# BleHidKeyboard.net
KiCad netlist of a schematic drawn in EAGLE
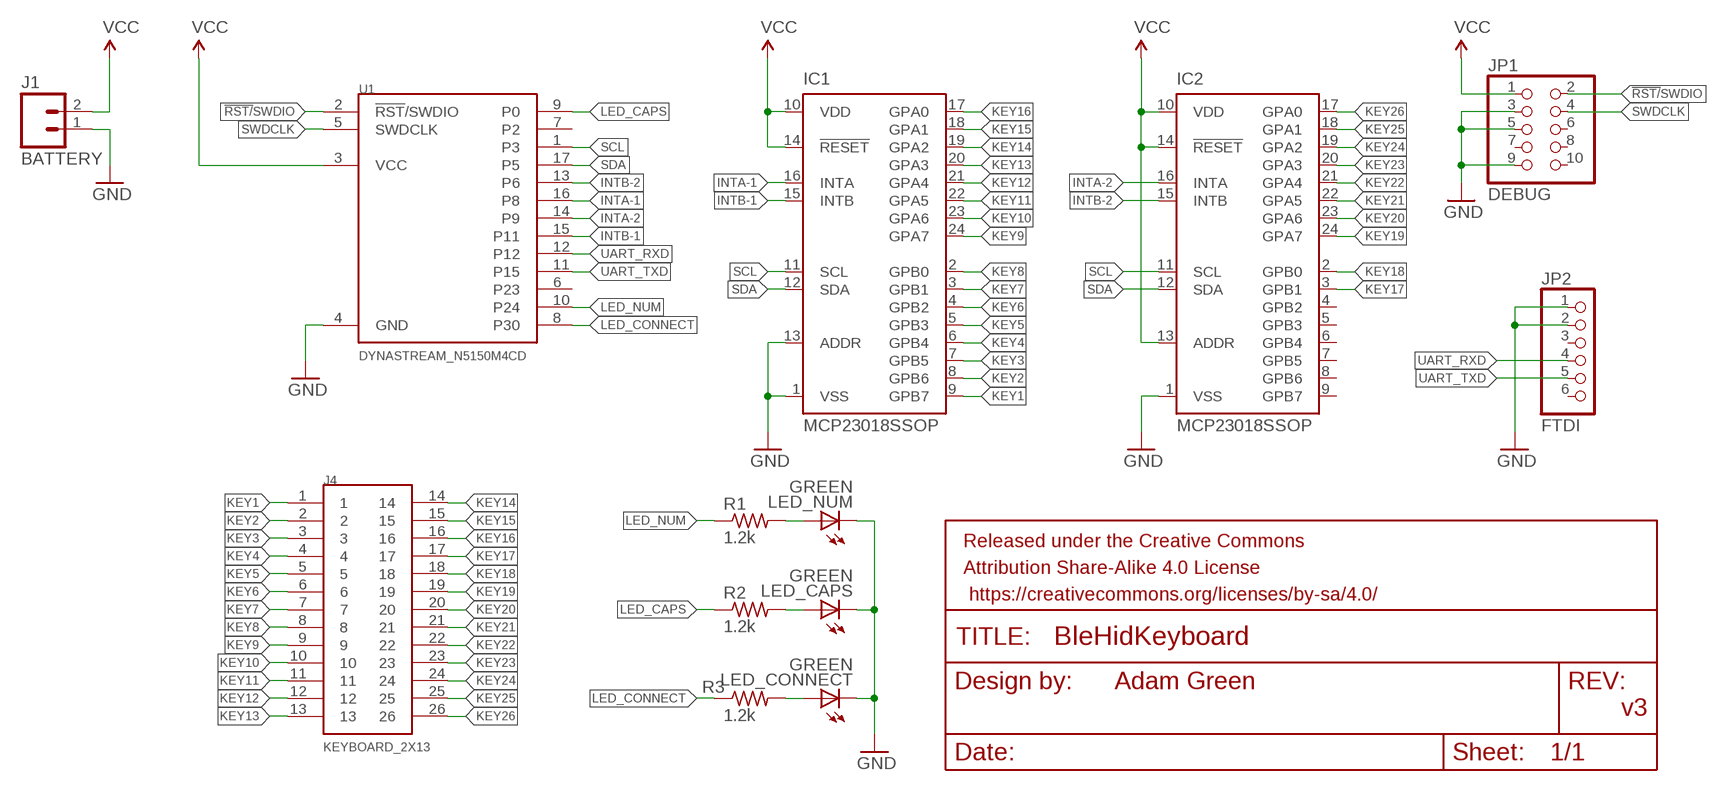
[diagram p0: schematic, sheet 1]

(export (version "E")
  (design (tool "Eeschema 10.0.6"))
  (components
    (comp (ref "IC1")
      (value "MCP23018SSOP")
      (footprint "eagle-import:SSOP24")
      (libsource (lib "eagle-import") (part "MCP23018SSOP"))
    )
    (comp (ref "IC2")
      (value "MCP23018SSOP")
      (footprint "eagle-import:SSOP24")
      (libsource (lib "eagle-import") (part "MCP23018SSOP"))
    )
    (comp (ref "J1")
      (value "BATTERY")
      (footprint "eagle-import:1X02_NO_SILK")
      (libsource (lib "eagle-import") (part "M021X02_NO_SILK"))
    )
    (comp (ref "J4")
      (value "KEYBOARD_2X13")
      (footprint "eagle-import:KEYBOARD_2X13")
      (libsource (lib "eagle-import") (part "KEYBOARD_2X13"))
    )
    (comp (ref "JP1")
      (value "DEBUG")
      (footprint "eagle-import:FTSH-105")
      (libsource (lib "eagle-import") (part "FTSH-105"))
    )
    (comp (ref "JP2")
      (value "FTDI")
      (footprint "eagle-import:1X06-CLEAN")
      (libsource (lib "eagle-import") (part "PINHD-1X6CLEAN"))
    )
    (comp (ref "LED_CAPS")
      (value "GREEN")
      (footprint "eagle-import:CHIPLED_1206")
      (libsource (lib "eagle-import") (part "LEDCHIPLED_1206"))
    )
    (comp (ref "LED_CONNECT")
      (value "GREEN")
      (footprint "eagle-import:CHIPLED_1206")
      (libsource (lib "eagle-import") (part "LEDCHIPLED_1206"))
    )
    (comp (ref "LED_NUM")
      (value "GREEN")
      (footprint "eagle-import:CHIPLED_1206")
      (libsource (lib "eagle-import") (part "LEDCHIPLED_1206"))
    )
    (comp (ref "R1")
      (value "1.2k")
      (footprint "eagle-import:R0805")
      (libsource (lib "eagle-import") (part "R-US_R0805"))
    )
    (comp (ref "R2")
      (value "1.2k")
      (footprint "eagle-import:R0805")
      (libsource (lib "eagle-import") (part "R-US_R0805"))
    )
    (comp (ref "R3")
      (value "1.2k")
      (footprint "eagle-import:R0805")
      (libsource (lib "eagle-import") (part "R-US_R0805"))
    )
    (comp (ref "U1")
      (value "DYNASTREAM_N5150M4CD")
      (footprint "eagle-import:N5150M4CD")
      (libsource (lib "eagle-import") (part "DYNASTREAM_N5150M4CD"))
    )
  )
  (nets
    (net (code "1") (name "/~{RST{slash}}SWDIO") (class "Default")
      (node (ref "JP1") (pin "2") (pinfunction "2_2") (pintype "passive"))
      (node (ref "U1") (pin "2") (pinfunction "~{RST}/SWDIO_2") (pintype "bidirectional"))
    )
    (net (code "2") (name "GND") (class "Default")
      (node (ref "IC1") (pin "1") (pinfunction "VSS_1") (pintype "input"))
      (node (ref "IC1") (pin "13") (pinfunction "ADDR_13") (pintype "input"))
      (node (ref "IC2") (pin "1") (pinfunction "VSS_1") (pintype "input"))
      (node (ref "J1") (pin "1") (pinfunction "1_1") (pintype "passive"))
      (node (ref "JP1") (pin "3") (pinfunction "3_3") (pintype "passive"))
      (node (ref "JP1") (pin "5") (pinfunction "5_5") (pintype "passive"))
      (node (ref "JP1") (pin "9") (pinfunction "9_9") (pintype "passive"))
      (node (ref "JP2") (pin "1") (pinfunction "1_1") (pintype "passive"))
      (node (ref "JP2") (pin "2") (pinfunction "2_2") (pintype "passive"))
      (node (ref "LED_CAPS") (pin "C") (pinfunction "C_C") (pintype "passive"))
      (node (ref "LED_CONNECT") (pin "C") (pinfunction "C_C") (pintype "passive"))
      (node (ref "LED_NUM") (pin "C") (pinfunction "C_C") (pintype "passive"))
      (node (ref "U1") (pin "4") (pinfunction "GND_4") (pintype "power_in"))
    )
    (net (code "3") (name "INTA-1") (class "Default")
      (node (ref "IC1") (pin "16") (pinfunction "INTA_16") (pintype "output"))
      (node (ref "U1") (pin "16") (pinfunction "P8_16") (pintype "bidirectional"))
    )
    (net (code "4") (name "INTA-2") (class "Default")
      (node (ref "IC2") (pin "16") (pinfunction "INTA_16") (pintype "output"))
      (node (ref "U1") (pin "14") (pinfunction "P9_14") (pintype "bidirectional"))
    )
    (net (code "5") (name "INTB-1") (class "Default")
      (node (ref "IC1") (pin "15") (pinfunction "INTB_15") (pintype "output"))
      (node (ref "U1") (pin "15") (pinfunction "P11_15") (pintype "bidirectional"))
    )
    (net (code "6") (name "INTB-2") (class "Default")
      (node (ref "IC2") (pin "15") (pinfunction "INTB_15") (pintype "output"))
      (node (ref "U1") (pin "13") (pinfunction "P6_13") (pintype "bidirectional"))
    )
    (net (code "7") (name "KEY1") (class "Default")
      (node (ref "IC1") (pin "9") (pinfunction "GPB7_9") (pintype "bidirectional"))
      (node (ref "J4") (pin "1") (pinfunction "1_1") (pintype "bidirectional"))
    )
    (net (code "8") (name "KEY2") (class "Default")
      (node (ref "IC1") (pin "8") (pinfunction "GPB6_8") (pintype "bidirectional"))
      (node (ref "J4") (pin "2") (pinfunction "2_2") (pintype "bidirectional"))
    )
    (net (code "9") (name "KEY3") (class "Default")
      (node (ref "IC1") (pin "7") (pinfunction "GPB5_7") (pintype "bidirectional"))
      (node (ref "J4") (pin "3") (pinfunction "3_3") (pintype "bidirectional"))
    )
    (net (code "10") (name "KEY4") (class "Default")
      (node (ref "IC1") (pin "6") (pinfunction "GPB4_6") (pintype "bidirectional"))
      (node (ref "J4") (pin "4") (pinfunction "4_4") (pintype "bidirectional"))
    )
    (net (code "11") (name "KEY5") (class "Default")
      (node (ref "IC1") (pin "5") (pinfunction "GPB3_5") (pintype "bidirectional"))
      (node (ref "J4") (pin "5") (pinfunction "5_5") (pintype "bidirectional"))
    )
    (net (code "12") (name "KEY6") (class "Default")
      (node (ref "IC1") (pin "4") (pinfunction "GPB2_4") (pintype "bidirectional"))
      (node (ref "J4") (pin "6") (pinfunction "6_6") (pintype "bidirectional"))
    )
    (net (code "13") (name "KEY7") (class "Default")
      (node (ref "IC1") (pin "3") (pinfunction "GPB1_3") (pintype "bidirectional"))
      (node (ref "J4") (pin "7") (pinfunction "7_7") (pintype "bidirectional"))
    )
    (net (code "14") (name "KEY8") (class "Default")
      (node (ref "IC1") (pin "2") (pinfunction "GPB0_2") (pintype "bidirectional"))
      (node (ref "J4") (pin "8") (pinfunction "8_8") (pintype "bidirectional"))
    )
    (net (code "15") (name "KEY9") (class "Default")
      (node (ref "IC1") (pin "24") (pinfunction "GPA7_24") (pintype "bidirectional"))
      (node (ref "J4") (pin "9") (pinfunction "9_9") (pintype "bidirectional"))
    )
    (net (code "16") (name "KEY10") (class "Default")
      (node (ref "IC1") (pin "23") (pinfunction "GPA6_23") (pintype "bidirectional"))
      (node (ref "J4") (pin "10") (pinfunction "10_10") (pintype "bidirectional"))
    )
    (net (code "17") (name "KEY11") (class "Default")
      (node (ref "IC1") (pin "22") (pinfunction "GPA5_22") (pintype "bidirectional"))
      (node (ref "J4") (pin "11") (pinfunction "11_11") (pintype "bidirectional"))
    )
    (net (code "18") (name "KEY12") (class "Default")
      (node (ref "IC1") (pin "21") (pinfunction "GPA4_21") (pintype "bidirectional"))
      (node (ref "J4") (pin "12") (pinfunction "12_12") (pintype "bidirectional"))
    )
    (net (code "19") (name "KEY13") (class "Default")
      (node (ref "IC1") (pin "20") (pinfunction "GPA3_20") (pintype "bidirectional"))
      (node (ref "J4") (pin "13") (pinfunction "13_13") (pintype "bidirectional"))
    )
    (net (code "20") (name "KEY14") (class "Default")
      (node (ref "IC1") (pin "19") (pinfunction "GPA2_19") (pintype "bidirectional"))
      (node (ref "J4") (pin "14") (pinfunction "14_14") (pintype "bidirectional"))
    )
    (net (code "21") (name "KEY15") (class "Default")
      (node (ref "IC1") (pin "18") (pinfunction "GPA1_18") (pintype "bidirectional"))
      (node (ref "J4") (pin "15") (pinfunction "15_15") (pintype "bidirectional"))
    )
    (net (code "22") (name "KEY16") (class "Default")
      (node (ref "IC1") (pin "17") (pinfunction "GPA0_17") (pintype "bidirectional"))
      (node (ref "J4") (pin "16") (pinfunction "16_16") (pintype "bidirectional"))
    )
    (net (code "23") (name "KEY17") (class "Default")
      (node (ref "IC2") (pin "3") (pinfunction "GPB1_3") (pintype "bidirectional"))
      (node (ref "J4") (pin "17") (pinfunction "17_17") (pintype "bidirectional"))
    )
    (net (code "24") (name "KEY18") (class "Default")
      (node (ref "IC2") (pin "2") (pinfunction "GPB0_2") (pintype "bidirectional"))
      (node (ref "J4") (pin "18") (pinfunction "18_18") (pintype "bidirectional"))
    )
    (net (code "25") (name "KEY19") (class "Default")
      (node (ref "IC2") (pin "24") (pinfunction "GPA7_24") (pintype "bidirectional"))
      (node (ref "J4") (pin "19") (pinfunction "19_19") (pintype "bidirectional"))
    )
    (net (code "26") (name "KEY20") (class "Default")
      (node (ref "IC2") (pin "23") (pinfunction "GPA6_23") (pintype "bidirectional"))
      (node (ref "J4") (pin "20") (pinfunction "20_20") (pintype "bidirectional"))
    )
    (net (code "27") (name "KEY21") (class "Default")
      (node (ref "IC2") (pin "22") (pinfunction "GPA5_22") (pintype "bidirectional"))
      (node (ref "J4") (pin "21") (pinfunction "21_21") (pintype "bidirectional"))
    )
    (net (code "28") (name "KEY22") (class "Default")
      (node (ref "IC2") (pin "21") (pinfunction "GPA4_21") (pintype "bidirectional"))
      (node (ref "J4") (pin "22") (pinfunction "22_22") (pintype "bidirectional"))
    )
    (net (code "29") (name "KEY23") (class "Default")
      (node (ref "IC2") (pin "20") (pinfunction "GPA3_20") (pintype "bidirectional"))
      (node (ref "J4") (pin "23") (pinfunction "23_23") (pintype "bidirectional"))
    )
    (net (code "30") (name "KEY24") (class "Default")
      (node (ref "IC2") (pin "19") (pinfunction "GPA2_19") (pintype "bidirectional"))
      (node (ref "J4") (pin "24") (pinfunction "24_24") (pintype "bidirectional"))
    )
    (net (code "31") (name "KEY25") (class "Default")
      (node (ref "IC2") (pin "18") (pinfunction "GPA1_18") (pintype "bidirectional"))
      (node (ref "J4") (pin "25") (pinfunction "25_25") (pintype "bidirectional"))
    )
    (net (code "32") (name "KEY26") (class "Default")
      (node (ref "IC2") (pin "17") (pinfunction "GPA0_17") (pintype "bidirectional"))
      (node (ref "J4") (pin "26") (pinfunction "26_26") (pintype "bidirectional"))
    )
    (net (code "33") (name "LED_CAPS") (class "Default")
      (node (ref "R2") (pin "1") (pinfunction "1_1") (pintype "passive"))
      (node (ref "U1") (pin "9") (pinfunction "P0_9") (pintype "bidirectional"))
    )
    (net (code "34") (name "LED_CONNECT") (class "Default")
      (node (ref "R3") (pin "1") (pinfunction "1_1") (pintype "passive"))
      (node (ref "U1") (pin "8") (pinfunction "P30_8") (pintype "bidirectional"))
    )
    (net (code "35") (name "LED_NUM") (class "Default")
      (node (ref "R1") (pin "1") (pinfunction "1_1") (pintype "passive"))
      (node (ref "U1") (pin "10") (pinfunction "P24_10") (pintype "bidirectional"))
    )
    (net (code "36") (name "Net-(LED_CAPS-PadA)") (class "Default")
      (node (ref "LED_CAPS") (pin "A") (pinfunction "A_A") (pintype "passive"))
      (node (ref "R2") (pin "2") (pinfunction "2_2") (pintype "passive"))
    )
    (net (code "37") (name "Net-(LED_CONNECT-PadA)") (class "Default")
      (node (ref "LED_CONNECT") (pin "A") (pinfunction "A_A") (pintype "passive"))
      (node (ref "R3") (pin "2") (pinfunction "2_2") (pintype "passive"))
    )
    (net (code "38") (name "Net-(LED_NUM-PadA)") (class "Default")
      (node (ref "LED_NUM") (pin "A") (pinfunction "A_A") (pintype "passive"))
      (node (ref "R1") (pin "2") (pinfunction "2_2") (pintype "passive"))
    )
    (net (code "39") (name "SCL") (class "Default")
      (node (ref "IC1") (pin "11") (pinfunction "SCL_11") (pintype "input"))
      (node (ref "IC2") (pin "11") (pinfunction "SCL_11") (pintype "input"))
      (node (ref "U1") (pin "1") (pinfunction "P3_1") (pintype "bidirectional"))
    )
    (net (code "40") (name "SDA") (class "Default")
      (node (ref "IC1") (pin "12") (pinfunction "SDA_12") (pintype "bidirectional"))
      (node (ref "IC2") (pin "12") (pinfunction "SDA_12") (pintype "bidirectional"))
      (node (ref "U1") (pin "17") (pinfunction "P5_17") (pintype "bidirectional"))
    )
    (net (code "41") (name "SWDCLK") (class "Default")
      (node (ref "JP1") (pin "4") (pinfunction "4_4") (pintype "passive"))
      (node (ref "U1") (pin "5") (pinfunction "SWDCLK_5") (pintype "input"))
    )
    (net (code "42") (name "UART_RXD") (class "Default")
      (node (ref "JP2") (pin "4") (pinfunction "4_4") (pintype "passive"))
      (node (ref "U1") (pin "12") (pinfunction "P12_12") (pintype "bidirectional"))
    )
    (net (code "43") (name "UART_TXD") (class "Default")
      (node (ref "JP2") (pin "5") (pinfunction "5_5") (pintype "passive"))
      (node (ref "U1") (pin "11") (pinfunction "P15_11") (pintype "bidirectional"))
    )
    (net (code "44") (name "VCC") (class "Default")
      (node (ref "IC1") (pin "10") (pinfunction "VDD_10") (pintype "input"))
      (node (ref "IC1") (pin "14") (pinfunction "~{RESET}_14") (pintype "input"))
      (node (ref "IC2") (pin "10") (pinfunction "VDD_10") (pintype "input"))
      (node (ref "IC2") (pin "13") (pinfunction "ADDR_13") (pintype "input"))
      (node (ref "IC2") (pin "14") (pinfunction "~{RESET}_14") (pintype "input"))
      (node (ref "J1") (pin "2") (pinfunction "2_2") (pintype "passive"))
      (node (ref "JP1") (pin "1") (pinfunction "1_1") (pintype "passive"))
      (node (ref "U1") (pin "3") (pinfunction "VCC_3") (pintype "power_in"))
    )
    (net (code "45") (name "unconnected-(IC2-GPB2-Pad4)") (class "Default")
      (node (ref "IC2") (pin "4") (pinfunction "GPB2_4") (pintype "bidirectional"))
    )
    (net (code "46") (name "unconnected-(IC2-GPB3-Pad5)") (class "Default")
      (node (ref "IC2") (pin "5") (pinfunction "GPB3_5") (pintype "bidirectional"))
    )
    (net (code "47") (name "unconnected-(IC2-GPB4-Pad6)") (class "Default")
      (node (ref "IC2") (pin "6") (pinfunction "GPB4_6") (pintype "bidirectional"))
    )
    (net (code "48") (name "unconnected-(IC2-GPB5-Pad7)") (class "Default")
      (node (ref "IC2") (pin "7") (pinfunction "GPB5_7") (pintype "bidirectional"))
    )
    (net (code "49") (name "unconnected-(IC2-GPB6-Pad8)") (class "Default")
      (node (ref "IC2") (pin "8") (pinfunction "GPB6_8") (pintype "bidirectional"))
    )
    (net (code "50") (name "unconnected-(IC2-GPB7-Pad9)") (class "Default")
      (node (ref "IC2") (pin "9") (pinfunction "GPB7_9") (pintype "bidirectional"))
    )
    (net (code "51") (name "unconnected-(JP1-Pad6)") (class "Default")
      (node (ref "JP1") (pin "6") (pinfunction "6_6") (pintype "passive"))
    )
    (net (code "52") (name "unconnected-(JP1-Pad7)") (class "Default")
      (node (ref "JP1") (pin "7") (pinfunction "7_7") (pintype "passive"))
    )
    (net (code "53") (name "unconnected-(JP1-Pad8)") (class "Default")
      (node (ref "JP1") (pin "8") (pinfunction "8_8") (pintype "passive"))
    )
    (net (code "54") (name "unconnected-(JP1-Pad10)") (class "Default")
      (node (ref "JP1") (pin "10") (pinfunction "10_10") (pintype "passive"))
    )
    (net (code "55") (name "unconnected-(JP2-Pad3)") (class "Default")
      (node (ref "JP2") (pin "3") (pinfunction "3_3") (pintype "passive"))
    )
    (net (code "56") (name "unconnected-(JP2-Pad6)") (class "Default")
      (node (ref "JP2") (pin "6") (pinfunction "6_6") (pintype "passive"))
    )
    (net (code "57") (name "unconnected-(U1-P2-Pad7)") (class "Default")
      (node (ref "U1") (pin "7") (pinfunction "P2_7") (pintype "bidirectional"))
    )
    (net (code "58") (name "unconnected-(U1-P23-Pad6)") (class "Default")
      (node (ref "U1") (pin "6") (pinfunction "P23_6") (pintype "bidirectional"))
    )
  )
)
